# Clap_operated_system.net
KiCad netlist of a schematic drawn in EAGLE
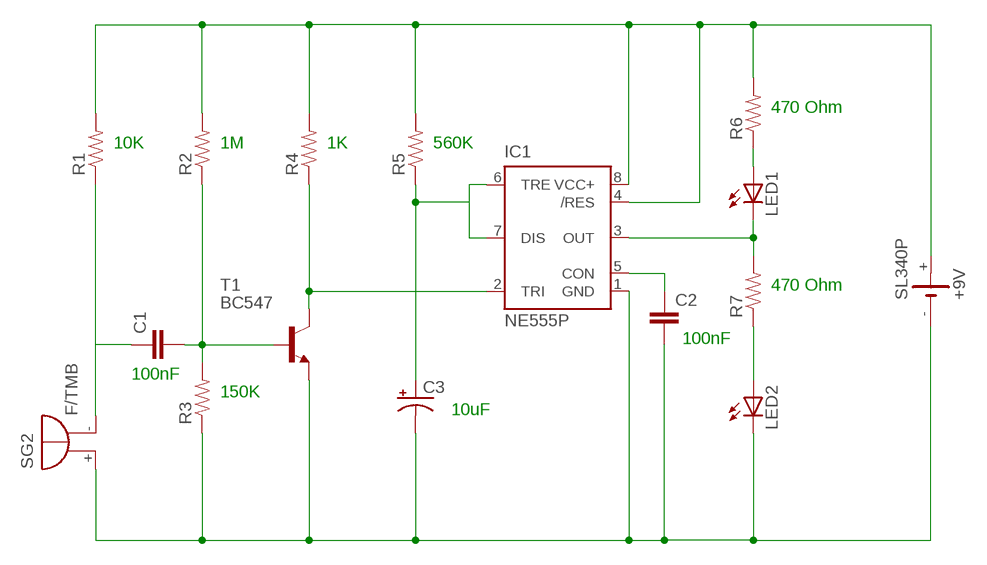
[diagram p0: schematic, sheet 1]

(export (version "E")
  (design (tool "Eeschema 10.0.6"))
  (components
    (comp (ref "+9V")
      (value "SL340P")
      (footprint "eagle-import:SL-340_P3.6V")
      (libsource (lib "eagle-import") (part "SL340P"))
    )
    (comp (ref "C1")
      (value "0.1UF-50V-20%(PTH)KIT-EZ")
      (footprint "eagle-import:CAP-PTH-SMALL-KIT")
      (libsource (lib "eagle-import") (part "0.1UF-50V-20%(PTH)KIT-EZ"))
    )
    (comp (ref "C2")
      (value "0.1UF-50V-20%(PTH)KIT-EZ")
      (footprint "eagle-import:CAP-PTH-SMALL-KIT")
      (libsource (lib "eagle-import") (part "0.1UF-50V-20%(PTH)KIT-EZ"))
    )
    (comp (ref "C3")
      (value "CAP_POLPTH1")
      (footprint "eagle-import:CPOL-RADIAL-100UF-25V")
      (libsource (lib "eagle-import") (part "CAP_POLPTH1"))
    )
    (comp (ref "IC1")
      (value "NE555P")
      (footprint "eagle-import:DIL-08")
      (fields (field (name "MF") "Arrow Electronics") (field (name "MPN") "NE555N"))
      (libsource (lib "eagle-import") (part "NE555P"))
    )
    (comp (ref "LED1")
      (value "LED5MM")
      (footprint "eagle-import:LED5MM")
      (libsource (lib "eagle-import") (part "LED5MM"))
    )
    (comp (ref "LED2")
      (value "LED5MM")
      (footprint "eagle-import:LED5MM")
      (libsource (lib "eagle-import") (part "LED5MM"))
    )
    (comp (ref "R1")
      (value "10KOHM1/6W5%(PTH)KIT")
      (footprint "eagle-import:AXIAL-0.3-KIT")
      (libsource (lib "eagle-import") (part "10KOHM1/6W5%(PTH)KIT"))
    )
    (comp (ref "R2")
      (value "10KOHM1/6W5%(PTH)KIT")
      (footprint "eagle-import:AXIAL-0.3-KIT")
      (libsource (lib "eagle-import") (part "10KOHM1/6W5%(PTH)KIT"))
    )
    (comp (ref "R3")
      (value "10KOHM1/6W5%(PTH)KIT")
      (footprint "eagle-import:AXIAL-0.3-KIT")
      (libsource (lib "eagle-import") (part "10KOHM1/6W5%(PTH)KIT"))
    )
    (comp (ref "R4")
      (value "10KOHM1/6W5%(PTH)KIT")
      (footprint "eagle-import:AXIAL-0.3-KIT")
      (libsource (lib "eagle-import") (part "10KOHM1/6W5%(PTH)KIT"))
    )
    (comp (ref "R5")
      (value "10KOHM1/6W5%(PTH)KIT")
      (footprint "eagle-import:AXIAL-0.3-KIT")
      (libsource (lib "eagle-import") (part "10KOHM1/6W5%(PTH)KIT"))
    )
    (comp (ref "R6")
      (value "10KOHM1/6W5%(PTH)KIT")
      (footprint "eagle-import:AXIAL-0.3-KIT")
      (libsource (lib "eagle-import") (part "10KOHM1/6W5%(PTH)KIT"))
    )
    (comp (ref "R7")
      (value "10KOHM1/6W5%(PTH)KIT")
      (footprint "eagle-import:AXIAL-0.3-KIT")
      (libsource (lib "eagle-import") (part "10KOHM1/6W5%(PTH)KIT"))
    )
    (comp (ref "SG2")
      (value "F/TMB")
      (footprint "eagle-import:F_TMB")
      (libsource (lib "eagle-import") (part "F/TMB"))
    )
    (comp (ref "T1")
      (value "BC547")
      (footprint "eagle-import:TO92")
      (libsource (lib "eagle-import") (part "BC547"))
    )
  )
  (nets
    (net (code "1") (name "Net-(C3-+)") (class "Default")
      (node (ref "C3") (pin "1") (pinfunction "+_1") (pintype "passive"))
      (node (ref "IC1") (pin "6") (pinfunction "TRE_6") (pintype "input"))
      (node (ref "IC1") (pin "7") (pinfunction "DIS_7") (pintype "input"))
      (node (ref "R5") (pin "P$1") (pinfunction "1_P$1") (pintype "passive"))
    )
    (net (code "2") (name "Net-(C3--)") (class "Default")
      (node (ref "+9V") (pin "-") (pinfunction "-_-") (pintype "passive"))
      (node (ref "C2") (pin "2") (pinfunction "2_2") (pintype "passive"))
      (node (ref "C3") (pin "2") (pinfunction "-_2") (pintype "passive"))
      (node (ref "IC1") (pin "1") (pinfunction "GND_1") (pintype "power_in"))
      (node (ref "LED2") (pin "K") (pinfunction "C_K") (pintype "passive"))
      (node (ref "R3") (pin "P$1") (pinfunction "1_P$1") (pintype "passive"))
      (node (ref "SG2") (pin "+") (pinfunction "+_+") (pintype "passive"))
      (node (ref "T1") (pin "1") (pinfunction "E_1") (pintype "passive"))
    )
    (net (code "3") (name "Net-(IC1-CON)") (class "Default")
      (node (ref "C2") (pin "1") (pinfunction "1_1") (pintype "passive"))
      (node (ref "IC1") (pin "5") (pinfunction "CON_5") (pintype "input"))
    )
    (net (code "4") (name "Net-(IC1-OUT)") (class "Default")
      (node (ref "IC1") (pin "3") (pinfunction "OUT_3") (pintype "output"))
      (node (ref "LED1") (pin "K") (pinfunction "C_K") (pintype "passive"))
      (node (ref "R7") (pin "P$2") (pinfunction "2_P$2") (pintype "passive"))
    )
    (net (code "5") (name "Net-(IC1-TRI)") (class "Default")
      (node (ref "IC1") (pin "2") (pinfunction "TRI_2") (pintype "input"))
      (node (ref "R4") (pin "P$1") (pinfunction "1_P$1") (pintype "passive"))
      (node (ref "T1") (pin "3") (pinfunction "C_3") (pintype "passive"))
    )
    (net (code "6") (name "Net-(IC1-VCC+)") (class "Default")
      (node (ref "+9V") (pin "+") (pinfunction "+_+") (pintype "passive"))
      (node (ref "IC1") (pin "4") (pinfunction "/RES_4") (pintype "input"))
      (node (ref "IC1") (pin "8") (pinfunction "VCC+_8") (pintype "power_in"))
      (node (ref "R1") (pin "P$2") (pinfunction "2_P$2") (pintype "passive"))
      (node (ref "R2") (pin "P$2") (pinfunction "2_P$2") (pintype "passive"))
      (node (ref "R4") (pin "P$2") (pinfunction "2_P$2") (pintype "passive"))
      (node (ref "R5") (pin "P$2") (pinfunction "2_P$2") (pintype "passive"))
      (node (ref "R6") (pin "P$2") (pinfunction "2_P$2") (pintype "passive"))
    )
    (net (code "7") (name "Net-(R1-1)") (class "Default")
      (node (ref "C1") (pin "1") (pinfunction "1_1") (pintype "passive"))
      (node (ref "R1") (pin "P$1") (pinfunction "1_P$1") (pintype "passive"))
      (node (ref "SG2") (pin "-") (pinfunction "-_-") (pintype "passive"))
    )
    (net (code "8") (name "Net-(R2-1)") (class "Default")
      (node (ref "C1") (pin "2") (pinfunction "2_2") (pintype "passive"))
      (node (ref "R2") (pin "P$1") (pinfunction "1_P$1") (pintype "passive"))
      (node (ref "R3") (pin "P$2") (pinfunction "2_P$2") (pintype "passive"))
      (node (ref "T1") (pin "2") (pinfunction "B_2") (pintype "passive"))
    )
    (net (code "9") (name "Net-(R6-1)") (class "Default")
      (node (ref "LED1") (pin "A") (pinfunction "A_A") (pintype "passive"))
      (node (ref "R6") (pin "P$1") (pinfunction "1_P$1") (pintype "passive"))
    )
    (net (code "10") (name "Net-(R7-1)") (class "Default")
      (node (ref "LED2") (pin "A") (pinfunction "A_A") (pintype "passive"))
      (node (ref "R7") (pin "P$1") (pinfunction "1_P$1") (pintype "passive"))
    )
  )
)
